# Flash.net
KiCad netlist of a schematic drawn in Altium Designer
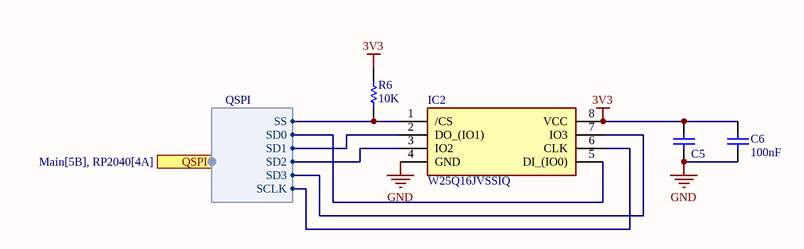
[diagram p0: Flash.SchDoc]

(export (version "E")
  (design (tool "Eeschema 10.0.6"))
  (components
    (comp (ref "C5")
      (value "100nF")
      (footprint "WCAP-CSGP_0603_L1.6W0.8H0.8_Reflow")
      (description "WCAP-CSGP Multilayer Ceramic Chip Capacitor, General Purpose, size 0603, X7R, 100nF, 50VDC")
      (fields
        (field (name "MANUFACTURER PART NUMBER") "885012206095")
        (field (name "MANUFACTURER") "Wurth Elektronik")
      )
      (libsource (lib "Altium_WCAP-CSGP (rev22f)") (part "885012206095"))
    )
    (comp (ref "C6")
      (value "100nF")
      (footprint "0402 cap")
      (libsource (lib "Custom Components") (part "Capacitor 0402 100nF"))
    )
    (comp (ref "IC2")
      (value "W25Q16JVSSIQ")
      (footprint "Custom Components:SOIC127P790X216-8N")
      (description "Integrated Circuit")
      (fields (field (name "MOUSER PART NUMBER") "454-W25Q16JVSSIQ"))
      (libsource (lib "Custom Components") (part "W25Q16JVSSIQ"))
    )
    (comp (ref "R6")
      (value "10K")
      (footprint "RESC0603(1608)_N")
      (description "Chipwiderstand, SMD, Baureihe MC, 1%")
      (fields (field (name "MANUFACTURER") "Multicomp"))
      (libsource (lib "Standardbauteile") (part "Res 10K"))
    )
  )
  (nets
    (net (code "2") (name "/SCLK") (class "Default")
      (node (ref "IC2") (pin "6") (pinfunction "CLK_6") (pintype "passive"))
    )
    (net (code "3") (name "/SD0") (class "Default")
      (node (ref "IC2") (pin "5") (pinfunction "DI_(IO0)_5") (pintype "passive"))
    )
    (net (code "4") (name "/SD1") (class "Default")
      (node (ref "IC2") (pin "2") (pinfunction "DO_(IO1)_2") (pintype "passive"))
    )
    (net (code "5") (name "/SD2") (class "Default")
      (node (ref "IC2") (pin "3") (pinfunction "IO2_3") (pintype "passive"))
    )
    (net (code "6") (name "/SD3") (class "Default")
      (node (ref "IC2") (pin "7") (pinfunction "IO3_7") (pintype "passive"))
    )
    (net (code "7") (name "/SS") (class "Default")
      (node (ref "IC2") (pin "1") (pinfunction "/CS_1") (pintype "passive"))
      (node (ref "R6") (pin "1") (pinfunction "1_1") (pintype "passive"))
    )
    (net (code "9") (name "3V3") (class "Default")
      (node (ref "C5") (pin "2") (pinfunction "2_2") (pintype "passive"))
      (node (ref "C6") (pin "2") (pinfunction "2_2") (pintype "passive"))
      (node (ref "IC2") (pin "8") (pinfunction "VCC_8") (pintype "passive"))
      (node (ref "R6") (pin "2") (pinfunction "2_2") (pintype "passive"))
    )
    (net (code "10") (name "GND") (class "Default")
      (node (ref "C5") (pin "1") (pinfunction "1_1") (pintype "passive"))
      (node (ref "C6") (pin "1") (pinfunction "1_1") (pintype "passive"))
      (node (ref "IC2") (pin "4") (pinfunction "GND_4") (pintype "passive"))
    )
  )
)
